# SchemaB-interace.net
KiCad netlist of a schematic drawn in Altium Designer
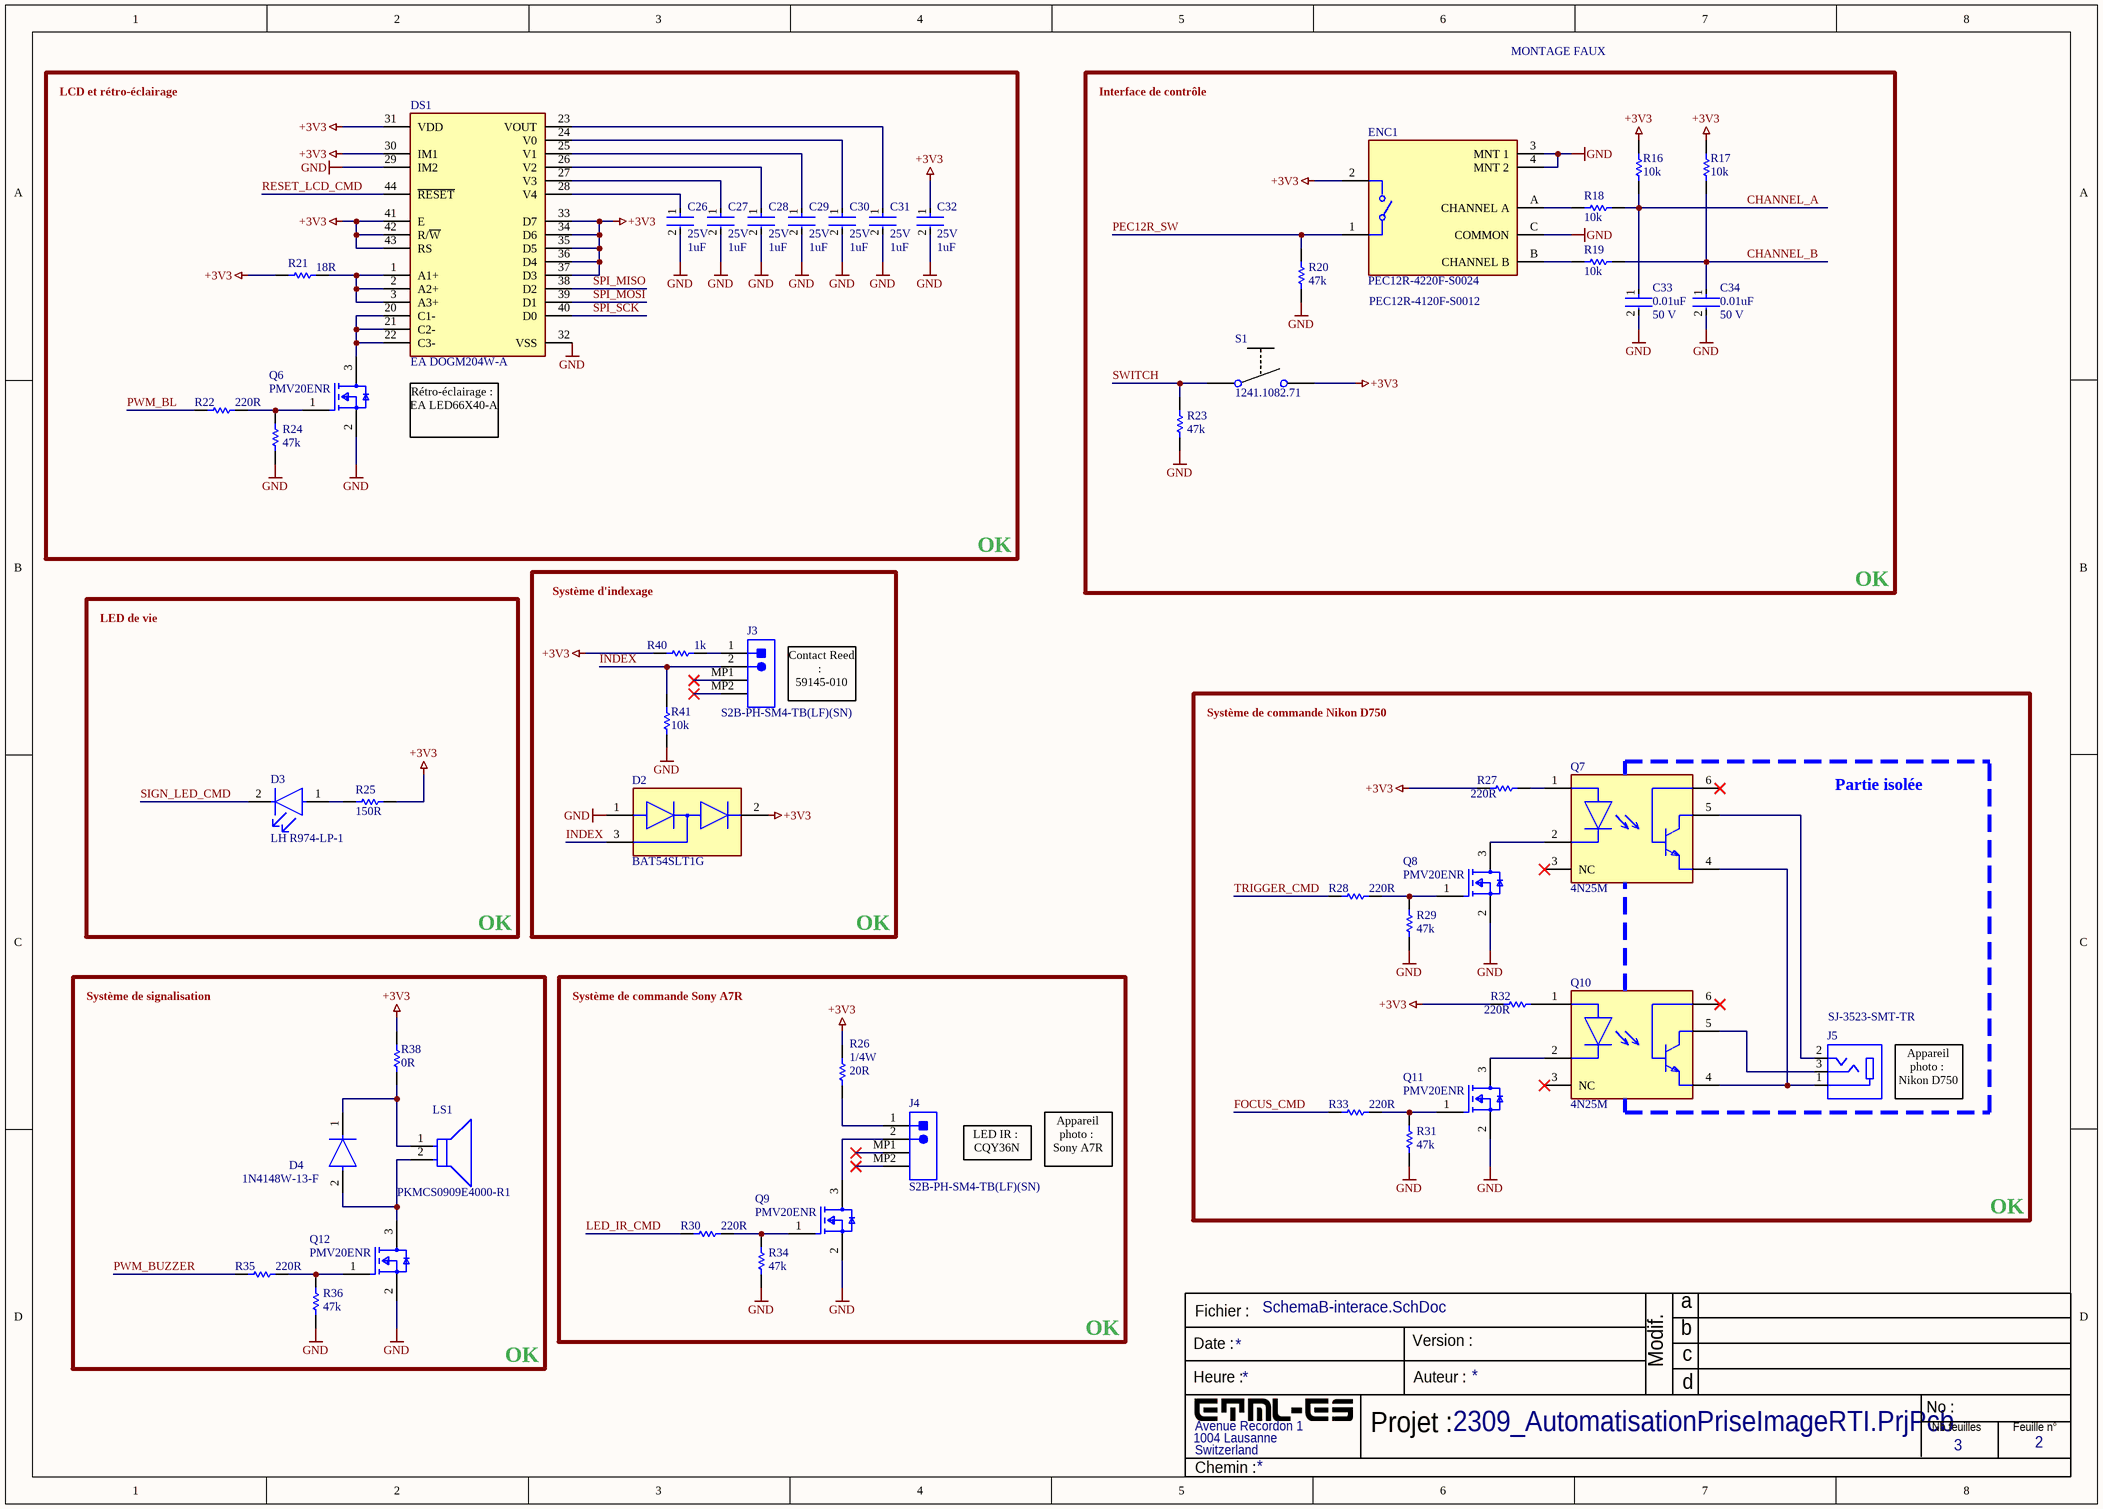
[diagram p0: SchemaB-interace.SchDoc]

(export (version "E")
  (design (tool "Eeschema 10.0.6"))
  (components
    (comp (ref "C26")
      (value "CL21F105ZAFNNNF")
      (footprint "FP-CL21-IPC_B")
      (description "CL21 Series 0805 1uF 25V -20/+80% Tolerance Y5V Multilayer Ceramic Chip Capacitor")
      (fields
        (field (name "VOLTAGE RATING") "25V")
        (field (name "CAPACITANCE") "1uF")
        (field (name "TOLERANCE") "80%")
      )
      (libsource (lib "Altium Content Vault") (part "b4654b650e69147ec39a6b967a45e02"))
    )
    (comp (ref "C27")
      (value "CL21F105ZAFNNNF")
      (footprint "FP-CL21-IPC_B")
      (description "CL21 Series 0805 1uF 25V -20/+80% Tolerance Y5V Multilayer Ceramic Chip Capacitor")
      (fields
        (field (name "VOLTAGE RATING") "25V")
        (field (name "CAPACITANCE") "1uF")
        (field (name "TOLERANCE") "80%")
      )
      (libsource (lib "Altium Content Vault") (part "b4654b650e69147ec39a6b967a45e02"))
    )
    (comp (ref "C28")
      (value "CL21F105ZAFNNNF")
      (footprint "FP-CL21-IPC_B")
      (description "CL21 Series 0805 1uF 25V -20/+80% Tolerance Y5V Multilayer Ceramic Chip Capacitor")
      (fields
        (field (name "VOLTAGE RATING") "25V")
        (field (name "CAPACITANCE") "1uF")
        (field (name "TOLERANCE") "80%")
      )
      (libsource (lib "Altium Content Vault") (part "b4654b650e69147ec39a6b967a45e02"))
    )
    (comp (ref "C29")
      (value "CL21F105ZAFNNNF")
      (footprint "FP-CL21-IPC_B")
      (description "CL21 Series 0805 1uF 25V -20/+80% Tolerance Y5V Multilayer Ceramic Chip Capacitor")
      (fields
        (field (name "VOLTAGE RATING") "25V")
        (field (name "CAPACITANCE") "1uF")
        (field (name "TOLERANCE") "80%")
      )
      (libsource (lib "Altium Content Vault") (part "b4654b650e69147ec39a6b967a45e02"))
    )
    (comp (ref "C30")
      (value "CL21F105ZAFNNNF")
      (footprint "FP-CL21-IPC_B")
      (description "CL21 Series 0805 1uF 25V -20/+80% Tolerance Y5V Multilayer Ceramic Chip Capacitor")
      (fields
        (field (name "VOLTAGE RATING") "25V")
        (field (name "CAPACITANCE") "1uF")
        (field (name "TOLERANCE") "80%")
      )
      (libsource (lib "Altium Content Vault") (part "b4654b650e69147ec39a6b967a45e02"))
    )
    (comp (ref "C31")
      (value "CL21F105ZAFNNNF")
      (footprint "FP-CL21-IPC_B")
      (description "CL21 Series 0805 1uF 25V -20/+80% Tolerance Y5V Multilayer Ceramic Chip Capacitor")
      (fields
        (field (name "VOLTAGE RATING") "25V")
        (field (name "CAPACITANCE") "1uF")
        (field (name "TOLERANCE") "80%")
      )
      (libsource (lib "Altium Content Vault") (part "b4654b650e69147ec39a6b967a45e02"))
    )
    (comp (ref "C32")
      (value "CL21F105ZAFNNNF")
      (footprint "FP-CL21-IPC_B")
      (description "CL21 Series 0805 1uF 25V -20/+80% Tolerance Y5V Multilayer Ceramic Chip Capacitor")
      (fields
        (field (name "VOLTAGE RATING") "25V")
        (field (name "CAPACITANCE") "1uF")
        (field (name "TOLERANCE") "80%")
      )
      (libsource (lib "Altium Content Vault") (part "b4654b650e69147ec39a6b967a45e02"))
    )
    (comp (ref "C33")
      (value "0.01uF")
      (footprint "FP-C0805C-DN-MFG")
      (description "CAP CER SMD 0805 .01UF X7R 5% 50")
      (fields
        (field (name "MANUFACTURER PART NUMBER") "C0805C103J5RAC7210")
        (field (name "MANUFACTURER") "KEMET")
        (field (name "VOLTAGE RATING") "50 V")
      )
      (libsource (lib "Altium Content Vault") (part "b4654b650e69147ec39a6b967a45e02"))
    )
    (comp (ref "C34")
      (value "0.01uF")
      (footprint "FP-C0805C-DN-MFG")
      (description "CAP CER SMD 0805 .01UF X7R 5% 50")
      (fields
        (field (name "MANUFACTURER PART NUMBER") "C0805C103J5RAC7210")
        (field (name "MANUFACTURER") "KEMET")
        (field (name "VOLTAGE RATING") "50 V")
      )
      (libsource (lib "Altium Content Vault") (part "b4654b650e69147ec39a6b967a45e02"))
    )
    (comp (ref "D2")
      (value "BAT54SLT1G")
      (footprint "FP-318-08-IPC_B")
      (description "DIODE ARRAY SCHOTTKY 30V SOT23-3")
      (libsource (lib "Altium Content Vault") (part "cd4ed45a2b9de5095685adb7d6d9b5b"))
    )
    (comp (ref "D3")
      (value "LH R974-LP-1")
      (footprint "FP-LH_R974-MFG")
      (description "LED RED DIFFUSED 0805 SMD")
      (libsource (lib "Altium Content Vault") (part "ab1c01a81903e929fc6c44469aada92"))
    )
    (comp (ref "D4")
      (value "1N4148W-13-F")
      (footprint "FP-SOD123-MFG")
      (description "DIODE GEN PURP 100V 150MA SOD123")
      (fields
        (field (name "OCTOPART") "https://octopart.com/1n4148w-13-f-diodes+inc.-2359612")
        (field (name "MANUFACTURER") "Diodes Inc.")
      )
      (libsource (lib "Altium Content Vault") (part "d7152d700b627762746794eb795d46e"))
    )
    (comp (ref "DS1")
      (value "EA DOGM204W-A")
      (footprint "EA DOGM204")
      (libsource (lib "SymbLib") (part "EA DOGM204"))
    )
    (comp (ref "ENC1")
      (value "PEC12R-4220F-S0024")
      (footprint "FP-PEC12R-4120F-S0012-MFG")
      (description "ROTARY ENCODER MECHANICAL 24PPR")
      (libsource (lib "SymbLib") (part "PEC12R-4220F-S0024"))
    )
    (comp (ref "J3")
      (value "S2B-PH-SM4-TB(LF)(SN)")
      (footprint "JST- S2B-PH-SM4-TB(LF)(SN)-2_V")
      (description "Male Header, Pitch 2 mm, 1 x 2 Position, Height 5.5 mm, -25 to 85 degC, RoHS, Tape and Reel")
      (libsource (lib "Altium Content Vault") (part "CN-1P-2M-R2"))
    )
    (comp (ref "J4")
      (value "S2B-PH-SM4-TB(LF)(SN)")
      (footprint "JST- S2B-PH-SM4-TB(LF)(SN)-2_V")
      (description "Male Header, Pitch 2 mm, 1 x 2 Position, Height 5.5 mm, -25 to 85 degC, RoHS, Tape and Reel")
      (libsource (lib "Altium Content Vault") (part "CN-1P-2M-R2"))
    )
    (comp (ref "J5")
      (value "SJ-3523-SMT-TR")
      (footprint "CUI_SJ-3523-SMT")
      (libsource (lib "SymbLib") (part "SJ-3523-SMT"))
    )
    (comp (ref "LS1")
      (value "PKMCS0909E4000-R1")
      (footprint "FP-PKMCS-MFG")
      (description "AUDIO PIEZO TRANSDUCER 12.5V SMD")
      (libsource (lib "Altium Content Vault") (part "1973c4b650225fd2ddacaff6b763965"))
    )
    (comp (ref "Q6")
      (value "PMV20ENR")
      (footprint "FP-SOT23-MFG")
      (description "MOSFET N-CH 30V SOT23")
      (libsource (lib "Altium Content Vault") (part "0a9ea7c96deaaede766a5b531c28de0"))
    )
    (comp (ref "Q7")
      (value "4N25M")
      (footprint "FP-646BX-MFG")
      (description "4N25M Optocoupler DC-IN 1-CH Transistor With Base DC-OUT 6-Pin PDIP Tube - Bulk")
      (libsource (lib "Altium Content Vault") (part "60cd882971725889b330b3d3aa4682b"))
    )
    (comp (ref "Q8")
      (value "PMV20ENR")
      (footprint "FP-SOT23-MFG")
      (description "MOSFET N-CH 30V SOT23")
      (libsource (lib "Altium Content Vault") (part "0a9ea7c96deaaede766a5b531c28de0"))
    )
    (comp (ref "Q9")
      (value "PMV20ENR")
      (footprint "FP-SOT23-MFG")
      (description "MOSFET N-CH 30V SOT23")
      (libsource (lib "Altium Content Vault") (part "0a9ea7c96deaaede766a5b531c28de0"))
    )
    (comp (ref "Q10")
      (value "4N25M")
      (footprint "FP-646BX-MFG")
      (description "4N25M Optocoupler DC-IN 1-CH Transistor With Base DC-OUT 6-Pin PDIP Tube - Bulk")
      (libsource (lib "Altium Content Vault") (part "60cd882971725889b330b3d3aa4682b"))
    )
    (comp (ref "Q11")
      (value "PMV20ENR")
      (footprint "FP-SOT23-MFG")
      (description "MOSFET N-CH 30V SOT23")
      (libsource (lib "Altium Content Vault") (part "0a9ea7c96deaaede766a5b531c28de0"))
    )
    (comp (ref "Q12")
      (value "PMV20ENR")
      (footprint "FP-SOT23-MFG")
      (description "MOSFET N-CH 30V SOT23")
      (libsource (lib "Altium Content Vault") (part "0a9ea7c96deaaede766a5b531c28de0"))
    )
    (comp (ref "R16")
      (value "RC0805JR-0710KL")
      (footprint "RESC2013X60X35ML10T20")
      (description "Chip Resistor, 10 KOhm, +/- 5%, 0.125 W, -55 to 155 degC, 0805 (2012 Metric), RoHS, Tape and Reel")
      (fields (field (name "MANUFACTURER") "Yageo") (field (name "RESISTANCE") "10k"))
      (libsource (lib "Altium Content Vault") (part "RES-2"))
    )
    (comp (ref "R17")
      (value "RC0805JR-0710KL")
      (footprint "RESC2013X60X35ML10T20")
      (description "Chip Resistor, 10 KOhm, +/- 5%, 0.125 W, -55 to 155 degC, 0805 (2012 Metric), RoHS, Tape and Reel")
      (fields (field (name "MANUFACTURER") "Yageo") (field (name "RESISTANCE") "10k"))
      (libsource (lib "Altium Content Vault") (part "RES-2"))
    )
    (comp (ref "R18")
      (value "RC0805JR-0710KL")
      (footprint "RESC2013X60X35ML10T20")
      (description "Chip Resistor, 10 KOhm, +/- 5%, 0.125 W, -55 to 155 degC, 0805 (2012 Metric), RoHS, Tape and Reel")
      (fields (field (name "MANUFACTURER") "Yageo") (field (name "RESISTANCE") "10k"))
      (libsource (lib "Altium Content Vault") (part "RES-2"))
    )
    (comp (ref "R19")
      (value "RC0805JR-0710KL")
      (footprint "RESC2013X60X35ML10T20")
      (description "Chip Resistor, 10 KOhm, +/- 5%, 0.125 W, -55 to 155 degC, 0805 (2012 Metric), RoHS, Tape and Reel")
      (fields (field (name "MANUFACTURER") "Yageo") (field (name "RESISTANCE") "10k"))
      (libsource (lib "Altium Content Vault") (part "RES-2"))
    )
    (comp (ref "R20")
      (value "47k")
      (footprint "RESC2013X60X35NL10T20")
      (description "Chip Resistor, 47 KOhm, +/- 1%, 0.125 W, -55 to 155 degC, 0805 (2012 Metric), RoHS, Tape and Reel")
      (fields (field (name "MANUFACTURER") "Yageo") (field (name "Comment") "RC0805FR-0747KL"))
      (libsource (lib "Altium Content Vault") (part "RES-2"))
    )
    (comp (ref "R21")
      (value "18R")
      (footprint "RESC2013X70X40ML20T20")
      (fields (field (name "MANUFACTURER") "Panasonic") (field (name "PART NUMBER") "ERJ6ENF18R0V"))
      (libsource (lib "Altium Content Vault") (part "RES"))
    )
    (comp (ref "R22")
      (value "220R")
      (footprint "RESC2013X70X40NL20T20")
      (fields (field (name "PART NUMBER") "ERJ6ENF2200V") (field (name "MANUFACTURER") "Panasonic"))
      (libsource (lib "Altium Content Vault") (part "RES"))
    )
    (comp (ref "R23")
      (value "47k")
      (footprint "RESC2013X60X35NL10T20")
      (description "Chip Resistor, 47 KOhm, +/- 1%, 0.125 W, -55 to 155 degC, 0805 (2012 Metric), RoHS, Tape and Reel")
      (fields (field (name "MANUFACTURER") "Yageo") (field (name "Comment") "RC0805FR-0747KL"))
      (libsource (lib "Altium Content Vault") (part "RES-2"))
    )
    (comp (ref "R24")
      (value "47k")
      (footprint "RESC2013X60X35NL10T20")
      (description "Chip Resistor, 47 KOhm, +/- 1%, 0.125 W, -55 to 155 degC, 0805 (2012 Metric), RoHS, Tape and Reel")
      (fields (field (name "MANUFACTURER") "Yageo") (field (name "Comment") "RC0805FR-0747KL"))
      (libsource (lib "Altium Content Vault") (part "RES-2"))
    )
    (comp (ref "R25")
      (value "150R")
      (footprint "RESC2013X60X35ML10T20")
      (fields (field (name "MANUFACTURER") "Yageo") (field (name "PART NUMBER") "RC0805JR-0775RL"))
      (libsource (lib "Altium Content Vault") (part "RES"))
    )
    (comp (ref "R26")
      (value "20R")
      (footprint "RESC2013X60X30ML20T20")
      (fields
        (field (name "PART NUMBER") "RK73B2ATTD200J")
        (field (name "MANUFACTURER") "KOA Speer")
        (field (name "PUISSANCE") "1/4W")
      )
      (libsource (lib "Altium Content Vault") (part "RES"))
    )
    (comp (ref "R27")
      (value "220R")
      (footprint "RESC2013X50X30NL20T20")
      (fields (field (name "PART NUMBER") "CRCW0805210RFKEA") (field (name "MANUFACTURER") "Vishay Dale"))
      (libsource (lib "Altium Content Vault") (part "RES"))
    )
    (comp (ref "R28")
      (value "220R")
      (footprint "RESC2013X70X40NL20T20")
      (fields (field (name "PART NUMBER") "ERJ6ENF2200V") (field (name "MANUFACTURER") "Panasonic"))
      (libsource (lib "Altium Content Vault") (part "RES"))
    )
    (comp (ref "R29")
      (value "47k")
      (footprint "RESC2013X60X35NL10T20")
      (description "Chip Resistor, 47 KOhm, +/- 1%, 0.125 W, -55 to 155 degC, 0805 (2012 Metric), RoHS, Tape and Reel")
      (fields (field (name "MANUFACTURER") "Yageo") (field (name "Comment") "RC0805FR-0747KL"))
      (libsource (lib "Altium Content Vault") (part "RES-2"))
    )
    (comp (ref "R30")
      (value "220R")
      (footprint "RESC2013X70X40NL20T20")
      (fields (field (name "PART NUMBER") "ERJ6ENF2200V") (field (name "MANUFACTURER") "Panasonic"))
      (libsource (lib "Altium Content Vault") (part "RES"))
    )
    (comp (ref "R31")
      (value "47k")
      (footprint "RESC2013X60X35NL10T20")
      (description "Chip Resistor, 47 KOhm, +/- 1%, 0.125 W, -55 to 155 degC, 0805 (2012 Metric), RoHS, Tape and Reel")
      (fields (field (name "MANUFACTURER") "Yageo") (field (name "Comment") "RC0805FR-0747KL"))
      (libsource (lib "Altium Content Vault") (part "RES-2"))
    )
    (comp (ref "R32")
      (value "220R")
      (footprint "RESC2013X50X30NL20T20")
      (fields (field (name "PART NUMBER") "CRCW0805210RFKEA") (field (name "MANUFACTURER") "Vishay Dale"))
      (libsource (lib "Altium Content Vault") (part "RES"))
    )
    (comp (ref "R33")
      (value "220R")
      (footprint "RESC2013X70X40NL20T20")
      (fields (field (name "PART NUMBER") "ERJ6ENF2200V") (field (name "MANUFACTURER") "Panasonic"))
      (libsource (lib "Altium Content Vault") (part "RES"))
    )
    (comp (ref "R34")
      (value "47k")
      (footprint "RESC2013X60X35NL10T20")
      (description "Chip Resistor, 47 KOhm, +/- 1%, 0.125 W, -55 to 155 degC, 0805 (2012 Metric), RoHS, Tape and Reel")
      (fields (field (name "MANUFACTURER") "Yageo") (field (name "Comment") "RC0805FR-0747KL"))
      (libsource (lib "Altium Content Vault") (part "RES-2"))
    )
    (comp (ref "R35")
      (value "220R")
      (footprint "RESC2013X70X40NL20T20")
      (fields (field (name "PART NUMBER") "ERJ6ENF2200V") (field (name "MANUFACTURER") "Panasonic"))
      (libsource (lib "Altium Content Vault") (part "RES"))
    )
    (comp (ref "R36")
      (value "47k")
      (footprint "RESC2013X60X35NL10T20")
      (description "Chip Resistor, 47 KOhm, +/- 1%, 0.125 W, -55 to 155 degC, 0805 (2012 Metric), RoHS, Tape and Reel")
      (fields (field (name "MANUFACTURER") "Yageo") (field (name "Comment") "RC0805FR-0747KL"))
      (libsource (lib "Altium Content Vault") (part "RES-2"))
    )
    (comp (ref "R38")
      (value "RC0805JR-070RL")
      (footprint "RESC2013X60X35ML10T20")
      (fields
        (field (name "RESISTANCE") "0R")
        (field (name "TOLERANCE") "5%")
        (field (name "MANUFACTURER") "Yageo")
      )
      (libsource (lib "Altium Content Vault") (part "RES-2"))
    )
    (comp (ref "R40")
      (value "RC0805FR-071KL")
      (footprint "RESC2013X60X35ML10T20")
      (description "Chip Resistor, 1 KOhm, +/- 1%, 125 mW, -55 to 155 degC, 0805 (2012 Metric), RoHS, Tape and Reel")
      (fields
        (field (name "RESISTANCE") "1k")
        (field (name "TOLERANCE") "1%")
        (field (name "MANUFACTURER") "Yageo")
      )
      (libsource (lib "Altium Content Vault") (part "RES-2"))
    )
    (comp (ref "R41")
      (value "RC0805JR-0710KL")
      (footprint "RESC2013X60X35ML10T20")
      (description "Chip Resistor, 10 KOhm, +/- 5%, 0.125 W, -55 to 155 degC, 0805 (2012 Metric), RoHS, Tape and Reel")
      (fields (field (name "MANUFACTURER") "Yageo") (field (name "RESISTANCE") "10k"))
      (libsource (lib "Altium Content Vault") (part "RES-2"))
    )
    (comp (ref "S1")
      (value "1241.1082.71")
      (footprint "Tact-sw 1241.1082")
      (libsource (lib "SymbLib") (part "Tact-sw 1241.1082"))
    )
  )
  (nets
    (net (code "1") (name "+3V3") (class "Default")
      (node (ref "C32") (pin "1") (pinfunction "1_1") (pintype "passive"))
      (node (ref "D2") (pin "2") (pinfunction "C_2") (pintype "passive"))
      (node (ref "DS1") (pin "30") (pinfunction "IM1_30") (pintype "passive"))
      (node (ref "DS1") (pin "31") (pinfunction "VDD_31") (pintype "passive"))
      (node (ref "DS1") (pin "33") (pinfunction "D7_33") (pintype "passive"))
      (node (ref "DS1") (pin "34") (pinfunction "D6_34") (pintype "passive"))
      (node (ref "DS1") (pin "35") (pinfunction "D5_35") (pintype "passive"))
      (node (ref "DS1") (pin "36") (pinfunction "D4_36") (pintype "passive"))
      (node (ref "DS1") (pin "37") (pinfunction "D3_37") (pintype "passive"))
      (node (ref "DS1") (pin "41") (pinfunction "E_41") (pintype "passive"))
      (node (ref "DS1") (pin "42") (pinfunction "R/~{W}_42") (pintype "passive"))
      (node (ref "DS1") (pin "43") (pinfunction "RS_43") (pintype "passive"))
      (node (ref "ENC1") (pin "2") (pinfunction "2_2") (pintype "passive"))
      (node (ref "R16") (pin "1") (pinfunction "1_1") (pintype "passive"))
      (node (ref "R17") (pin "1") (pinfunction "1_1") (pintype "passive"))
      (node (ref "R21") (pin "1") (pinfunction "1_1") (pintype "passive"))
      (node (ref "R25") (pin "2") (pinfunction "2_2") (pintype "passive"))
      (node (ref "R26") (pin "2") (pinfunction "2_2") (pintype "passive"))
      (node (ref "R27") (pin "1") (pinfunction "1_1") (pintype "passive"))
      (node (ref "R32") (pin "1") (pinfunction "1_1") (pintype "passive"))
      (node (ref "R38") (pin "2") (pinfunction "2_2") (pintype "passive"))
      (node (ref "R40") (pin "1") (pinfunction "1_1") (pintype "passive"))
      (node (ref "S1") (pin "2") (pinfunction "2_2") (pintype "passive"))
    )
    (net (code "2") (name "/CHANNEL_A") (class "Default")
      (node (ref "C33") (pin "1") (pinfunction "1_1") (pintype "passive"))
      (node (ref "R16") (pin "2") (pinfunction "2_2") (pintype "passive"))
      (node (ref "R18") (pin "1") (pinfunction "1_1") (pintype "passive"))
    )
    (net (code "3") (name "/CHANNEL_B") (class "Default")
      (node (ref "C34") (pin "1") (pinfunction "1_1") (pintype "passive"))
      (node (ref "R17") (pin "2") (pinfunction "2_2") (pintype "passive"))
      (node (ref "R19") (pin "1") (pinfunction "1_1") (pintype "passive"))
    )
    (net (code "4") (name "/FOCUS_CMD") (class "Default")
      (node (ref "R33") (pin "1") (pinfunction "1_1") (pintype "passive"))
    )
    (net (code "5") (name "/INDEX") (class "Default")
      (node (ref "D2") (pin "3") (pinfunction "CATHODE/ANODE_3") (pintype "passive"))
      (node (ref "J3") (pin "2") (pinfunction "2_2") (pintype "passive"))
      (node (ref "R41") (pin "1") (pinfunction "1_1") (pintype "passive"))
    )
    (net (code "6") (name "/LED_IR_CMD") (class "Default")
      (node (ref "R30") (pin "1") (pinfunction "1_1") (pintype "passive"))
    )
    (net (code "7") (name "/PEC12R_SW") (class "Default")
      (node (ref "ENC1") (pin "1") (pinfunction "1_1") (pintype "passive"))
      (node (ref "R20") (pin "2") (pinfunction "2_2") (pintype "passive"))
    )
    (net (code "8") (name "/PWM_BL") (class "Default")
      (node (ref "R22") (pin "1") (pinfunction "1_1") (pintype "passive"))
    )
    (net (code "9") (name "/PWM_BUZZER") (class "Default")
      (node (ref "R35") (pin "1") (pinfunction "1_1") (pintype "passive"))
    )
    (net (code "10") (name "/RESET_LCD_CMD") (class "Default")
      (node (ref "DS1") (pin "44") (pinfunction "~{RESET}_44") (pintype "passive"))
    )
    (net (code "11") (name "/SIGN_LED_CMD") (class "Default")
      (node (ref "D3") (pin "2") (pinfunction "C_2") (pintype "passive"))
    )
    (net (code "12") (name "/SPI_MISO") (class "Default")
      (node (ref "DS1") (pin "38") (pinfunction "D2_38") (pintype "passive"))
    )
    (net (code "13") (name "/SPI_MOSI") (class "Default")
      (node (ref "DS1") (pin "39") (pinfunction "D1_39") (pintype "passive"))
    )
    (net (code "14") (name "/SPI_SCK") (class "Default")
      (node (ref "DS1") (pin "40") (pinfunction "D0_40") (pintype "passive"))
    )
    (net (code "15") (name "/SWITCH") (class "Default")
      (node (ref "R23") (pin "2") (pinfunction "2_2") (pintype "passive"))
      (node (ref "S1") (pin "1") (pinfunction "1_1") (pintype "passive"))
    )
    (net (code "16") (name "/TRIGGER_CMD") (class "Default")
      (node (ref "R28") (pin "1") (pinfunction "1_1") (pintype "passive"))
    )
    (net (code "17") (name "GND") (class "Default")
      (node (ref "C26") (pin "2") (pinfunction "2_2") (pintype "passive"))
      (node (ref "C27") (pin "2") (pinfunction "2_2") (pintype "passive"))
      (node (ref "C28") (pin "2") (pinfunction "2_2") (pintype "passive"))
      (node (ref "C29") (pin "2") (pinfunction "2_2") (pintype "passive"))
      (node (ref "C30") (pin "2") (pinfunction "2_2") (pintype "passive"))
      (node (ref "C31") (pin "2") (pinfunction "2_2") (pintype "passive"))
      (node (ref "C32") (pin "2") (pinfunction "2_2") (pintype "passive"))
      (node (ref "C33") (pin "2") (pinfunction "2_2") (pintype "passive"))
      (node (ref "C34") (pin "2") (pinfunction "2_2") (pintype "passive"))
      (node (ref "D2") (pin "1") (pinfunction "A_1") (pintype "passive"))
      (node (ref "DS1") (pin "29") (pinfunction "IM2_29") (pintype "passive"))
      (node (ref "DS1") (pin "32") (pinfunction "VSS_32") (pintype "passive"))
      (node (ref "ENC1") (pin "3") (pinfunction "MNT_1_3") (pintype "passive"))
      (node (ref "ENC1") (pin "4") (pinfunction "MNT_2_4") (pintype "passive"))
      (node (ref "ENC1") (pin "C") (pinfunction "COMMON_C") (pintype "passive"))
      (node (ref "Q11") (pin "2") (pinfunction "S_2") (pintype "passive"))
      (node (ref "Q12") (pin "2") (pinfunction "S_2") (pintype "passive"))
      (node (ref "Q6") (pin "2") (pinfunction "S_2") (pintype "passive"))
      (node (ref "Q8") (pin "2") (pinfunction "S_2") (pintype "passive"))
      (node (ref "Q9") (pin "2") (pinfunction "S_2") (pintype "passive"))
      (node (ref "R20") (pin "1") (pinfunction "1_1") (pintype "passive"))
      (node (ref "R23") (pin "1") (pinfunction "1_1") (pintype "passive"))
      (node (ref "R24") (pin "1") (pinfunction "1_1") (pintype "passive"))
      (node (ref "R29") (pin "1") (pinfunction "1_1") (pintype "passive"))
      (node (ref "R31") (pin "1") (pinfunction "1_1") (pintype "passive"))
      (node (ref "R34") (pin "1") (pinfunction "1_1") (pintype "passive"))
      (node (ref "R36") (pin "1") (pinfunction "1_1") (pintype "passive"))
      (node (ref "R41") (pin "2") (pinfunction "2_2") (pintype "passive"))
    )
    (net (code "18") (name "Net-(D3-A)") (class "Default")
      (node (ref "D3") (pin "1") (pinfunction "A_1") (pintype "passive"))
      (node (ref "R25") (pin "1") (pinfunction "1_1") (pintype "passive"))
    )
    (net (code "19") (name "Net-(D4-A)") (class "Default")
      (node (ref "D4") (pin "2") (pinfunction "A_2") (pintype "passive"))
      (node (ref "LS1") (pin "2") (pinfunction "A_2") (pintype "passive"))
      (node (ref "Q12") (pin "3") (pinfunction "D_3") (pintype "passive"))
    )
    (net (code "20") (name "Net-(D4-C)") (class "Default")
      (node (ref "D4") (pin "1") (pinfunction "C_1") (pintype "passive"))
      (node (ref "LS1") (pin "1") (pinfunction "C_1") (pintype "passive"))
      (node (ref "R38") (pin "1") (pinfunction "1_1") (pintype "passive"))
    )
    (net (code "21") (name "Net-(DS1-A1+)") (class "Default")
      (node (ref "DS1") (pin "1") (pinfunction "A1+_1") (pintype "passive"))
      (node (ref "DS1") (pin "2") (pinfunction "A2+_2") (pintype "passive"))
      (node (ref "DS1") (pin "3") (pinfunction "A3+_3") (pintype "passive"))
      (node (ref "R21") (pin "2") (pinfunction "2_2") (pintype "passive"))
    )
    (net (code "22") (name "Net-(DS1-C1-)") (class "Default")
      (node (ref "DS1") (pin "20") (pinfunction "C1-_20") (pintype "passive"))
      (node (ref "DS1") (pin "21") (pinfunction "C2-_21") (pintype "passive"))
      (node (ref "DS1") (pin "22") (pinfunction "C3-_22") (pintype "passive"))
      (node (ref "Q6") (pin "3") (pinfunction "D_3") (pintype "passive"))
    )
    (net (code "23") (name "Net-(DS1-V0)") (class "Default")
      (node (ref "C30") (pin "1") (pinfunction "1_1") (pintype "passive"))
      (node (ref "DS1") (pin "24") (pinfunction "V0_24") (pintype "passive"))
    )
    (net (code "24") (name "Net-(DS1-V1)") (class "Default")
      (node (ref "C29") (pin "1") (pinfunction "1_1") (pintype "passive"))
      (node (ref "DS1") (pin "25") (pinfunction "V1_25") (pintype "passive"))
    )
    (net (code "25") (name "Net-(DS1-V2)") (class "Default")
      (node (ref "C28") (pin "1") (pinfunction "1_1") (pintype "passive"))
      (node (ref "DS1") (pin "26") (pinfunction "V2_26") (pintype "passive"))
    )
    (net (code "26") (name "Net-(DS1-V3)") (class "Default")
      (node (ref "C27") (pin "1") (pinfunction "1_1") (pintype "passive"))
      (node (ref "DS1") (pin "27") (pinfunction "V3_27") (pintype "passive"))
    )
    (net (code "27") (name "Net-(DS1-V4)") (class "Default")
      (node (ref "C26") (pin "1") (pinfunction "1_1") (pintype "passive"))
      (node (ref "DS1") (pin "28") (pinfunction "V4_28") (pintype "passive"))
    )
    (net (code "28") (name "Net-(DS1-VOUT)") (class "Default")
      (node (ref "C31") (pin "1") (pinfunction "1_1") (pintype "passive"))
      (node (ref "DS1") (pin "23") (pinfunction "VOUT_23") (pintype "passive"))
    )
    (net (code "29") (name "Net-(ENC1-CHANNEL_A)") (class "Default")
      (node (ref "ENC1") (pin "A") (pinfunction "CHANNEL_A_A") (pintype "passive"))
      (node (ref "R18") (pin "2") (pinfunction "2_2") (pintype "passive"))
    )
    (net (code "30") (name "Net-(ENC1-CHANNEL_B)") (class "Default")
      (node (ref "ENC1") (pin "B") (pinfunction "CHANNEL_B_B") (pintype "passive"))
      (node (ref "R19") (pin "2") (pinfunction "2_2") (pintype "passive"))
    )
    (net (code "31") (name "Net-(J3-Pad1)") (class "Default")
      (node (ref "J3") (pin "1") (pinfunction "1_1") (pintype "passive"))
      (node (ref "R40") (pin "2") (pinfunction "2_2") (pintype "passive"))
    )
    (net (code "32") (name "Net-(J4-Pad1)") (class "Default")
      (node (ref "J4") (pin "1") (pinfunction "1_1") (pintype "passive"))
      (node (ref "R26") (pin "1") (pinfunction "1_1") (pintype "passive"))
    )
    (net (code "33") (name "Net-(J5-Pad2)") (class "Default")
      (node (ref "J5") (pin "2") (pinfunction "2_2") (pintype "passive"))
      (node (ref "Q7") (pin "5") (pinfunction "C_5") (pintype "passive"))
    )
    (net (code "34") (name "Net-(J5-Pad3)") (class "Default")
      (node (ref "J5") (pin "3") (pinfunction "3_3") (pintype "passive"))
      (node (ref "Q10") (pin "5") (pinfunction "C_5") (pintype "passive"))
    )
    (net (code "35") (name "Net-(Q6-G)") (class "Default")
      (node (ref "Q6") (pin "1") (pinfunction "G_1") (pintype "passive"))
      (node (ref "R22") (pin "2") (pinfunction "2_2") (pintype "passive"))
      (node (ref "R24") (pin "2") (pinfunction "2_2") (pintype "passive"))
    )
    (net (code "36") (name "Net-(Q7-A)") (class "Default")
      (node (ref "Q7") (pin "1") (pinfunction "A_1") (pintype "passive"))
      (node (ref "R27") (pin "2") (pinfunction "2_2") (pintype "passive"))
    )
    (net (code "37") (name "Net-(Q8-D)") (class "Default")
      (node (ref "Q7") (pin "2") (pinfunction "C_2") (pintype "passive"))
      (node (ref "Q8") (pin "3") (pinfunction "D_3") (pintype "passive"))
    )
    (net (code "38") (name "Net-(Q8-G)") (class "Default")
      (node (ref "Q8") (pin "1") (pinfunction "G_1") (pintype "passive"))
      (node (ref "R28") (pin "2") (pinfunction "2_2") (pintype "passive"))
      (node (ref "R29") (pin "2") (pinfunction "2_2") (pintype "passive"))
    )
    (net (code "39") (name "Net-(Q9-D)") (class "Default")
      (node (ref "J4") (pin "2") (pinfunction "2_2") (pintype "passive"))
      (node (ref "Q9") (pin "3") (pinfunction "D_3") (pintype "passive"))
    )
    (net (code "40") (name "Net-(Q9-G)") (class "Default")
      (node (ref "Q9") (pin "1") (pinfunction "G_1") (pintype "passive"))
      (node (ref "R30") (pin "2") (pinfunction "2_2") (pintype "passive"))
      (node (ref "R34") (pin "2") (pinfunction "2_2") (pintype "passive"))
    )
    (net (code "41") (name "Net-(Q10-A)") (class "Default")
      (node (ref "Q10") (pin "1") (pinfunction "A_1") (pintype "passive"))
      (node (ref "R32") (pin "2") (pinfunction "2_2") (pintype "passive"))
    )
    (net (code "42") (name "Net-(Q10-E)") (class "Default")
      (node (ref "J5") (pin "1") (pinfunction "1_1") (pintype "passive"))
      (node (ref "Q10") (pin "4") (pinfunction "E_4") (pintype "passive"))
      (node (ref "Q7") (pin "4") (pinfunction "E_4") (pintype "passive"))
    )
    (net (code "43") (name "Net-(Q11-D)") (class "Default")
      (node (ref "Q10") (pin "2") (pinfunction "C_2") (pintype "passive"))
      (node (ref "Q11") (pin "3") (pinfunction "D_3") (pintype "passive"))
    )
    (net (code "44") (name "Net-(Q11-G)") (class "Default")
      (node (ref "Q11") (pin "1") (pinfunction "G_1") (pintype "passive"))
      (node (ref "R31") (pin "2") (pinfunction "2_2") (pintype "passive"))
      (node (ref "R33") (pin "2") (pinfunction "2_2") (pintype "passive"))
    )
    (net (code "45") (name "Net-(Q12-G)") (class "Default")
      (node (ref "Q12") (pin "1") (pinfunction "G_1") (pintype "passive"))
      (node (ref "R35") (pin "2") (pinfunction "2_2") (pintype "passive"))
      (node (ref "R36") (pin "2") (pinfunction "2_2") (pintype "passive"))
    )
    (net (code "46") (name "unconnected-(J3-PadMP1)") (class "Default")
      (node (ref "J3") (pin "MP1") (pinfunction "MP1_MP1") (pintype "passive+no_connect"))
    )
    (net (code "47") (name "unconnected-(J3-PadMP2)") (class "Default")
      (node (ref "J3") (pin "MP2") (pinfunction "MP2_MP2") (pintype "passive+no_connect"))
    )
    (net (code "48") (name "unconnected-(J4-PadMP1)") (class "Default")
      (node (ref "J4") (pin "MP1") (pinfunction "MP1_MP1") (pintype "passive+no_connect"))
    )
    (net (code "49") (name "unconnected-(J4-PadMP2)") (class "Default")
      (node (ref "J4") (pin "MP2") (pinfunction "MP2_MP2") (pintype "passive+no_connect"))
    )
    (net (code "50") (name "unconnected-(Q7-B-Pad6)") (class "Default")
      (node (ref "Q7") (pin "6") (pinfunction "B_6") (pintype "passive+no_connect"))
    )
    (net (code "51") (name "unconnected-(Q7-NC-Pad3)") (class "Default")
      (node (ref "Q7") (pin "3") (pinfunction "NC_3") (pintype "passive+no_connect"))
    )
    (net (code "52") (name "unconnected-(Q10-B-Pad6)") (class "Default")
      (node (ref "Q10") (pin "6") (pinfunction "B_6") (pintype "passive+no_connect"))
    )
    (net (code "53") (name "unconnected-(Q10-NC-Pad3)") (class "Default")
      (node (ref "Q10") (pin "3") (pinfunction "NC_3") (pintype "passive+no_connect"))
    )
  )
)
